# 1A20J16_1A21J0_A.net
KiCad netlist of a schematic drawn in Altium Designer
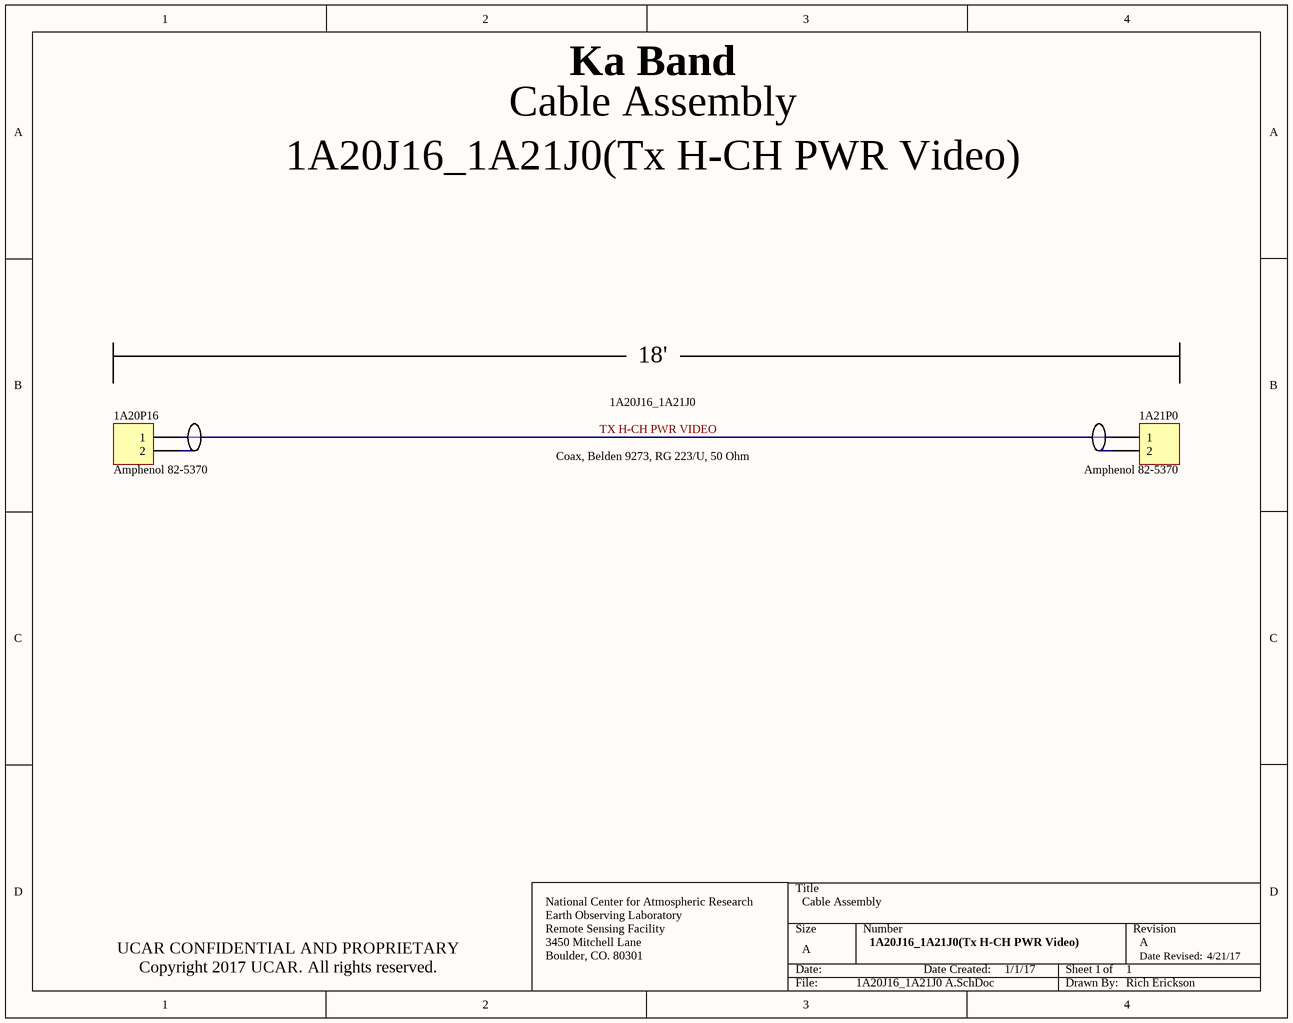
[diagram p0: 1A20J16_1A21J0 A.SchDoc]

(export (version "E")
  (design (tool "Eeschema 10.0.6"))
  (components
    (comp (ref "1A20P16")
      (value "Amphenol 82-5370")
      (footprint "HDR1X2")
      (description "Header, 2-Pin")
      (fields (field (name "PUBLISHER") "Altium Limited"))
      (libsource (lib "Miscellaneous Connectors") (part "Header 2"))
    )
    (comp (ref "1A21P0")
      (value "Amphenol 82-5370")
      (footprint "HDR1X2")
      (description "Header, 2-Pin")
      (fields (field (name "PUBLISHER") "Altium Limited"))
      (libsource (lib "") (part "Header 2_1"))
    )
  )
  (nets
    (net (code "1") (name "/TX H-CH PWR VIDEO") (class "Default")
      (node (ref "1A20P16") (pin "1") (pinfunction "1_1") (pintype "passive"))
      (node (ref "1A21P0") (pin "1") (pinfunction "1_1") (pintype "passive"))
    )
    (net (code "2") (name "unconnected-(1A20P16-Pad2)") (class "Default")
      (node (ref "1A20P16") (pin "2") (pinfunction "2_2") (pintype "passive"))
    )
    (net (code "3") (name "unconnected-(1A21P0-Pad2)") (class "Default")
      (node (ref "1A21P0") (pin "2") (pinfunction "2_2") (pintype "passive"))
    )
  )
)
